# SENSOR.net
KiCad netlist of a schematic drawn in Altium Designer
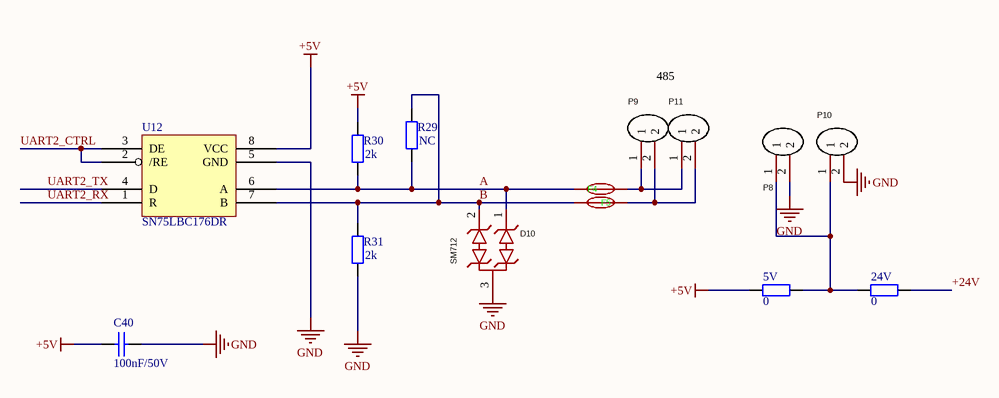
[diagram p0: SENSOR.SchDoc]

(export (version "E")
  (design (tool "Eeschema 10.0.6"))
  (components
    (comp (ref "5V")
      (value "0")
      (footprint "R-0805")
      (description "电阻")
      (fields (field (name "PUBLISHER") "Altium Limited"))
      (libsource (lib "") (part "RES_1"))
    )
    (comp (ref "24V")
      (value "0")
      (footprint "R-0805")
      (description "电阻")
      (fields (field (name "PUBLISHER") "Altium Limited"))
      (libsource (lib "") (part "RES_1"))
    )
    (comp (ref "C40")
      (value "100nF/50V")
      (footprint "C-0805")
      (description "电容")
      (libsource (lib "泰开常用器件") (part "C普通电容"))
    )
    (comp (ref "D10")
      (value "SM712")
      (footprint "SOT-23-3")
      (fields (field (name "MANUFACTURER") "宏迦橙"))
      (libsource (lib "altium-import") (part "root_2_SM712_C7420375_"))
    )
    (comp (ref "F4")
      (value "SMD1206-020-48")
      (footprint "F1206")
      (fields (field (name "MANUFACTURER") "宏嘉诚"))
      (libsource (lib "altium-import") (part "root_0_SMD1206-020-48_"))
    )
    (comp (ref "F5")
      (value "SMD1206-020-48")
      (footprint "F1206")
      (fields (field (name "MANUFACTURER") "宏嘉诚"))
      (libsource (lib "altium-import") (part "root_0_SMD1206-020-48_"))
    )
    (comp (ref "P8")
      (value "WJ500V-5.08-2P")
      (footprint "KF128-2P DG128")
      (fields (field (name "MANUFACTURER") "KANGNEX(康奈克斯电气)"))
      (libsource (lib "泰开常用器件") (part "WJ500V-5.08-2P"))
    )
    (comp (ref "P9")
      (value "WJ500V-5.08-2P")
      (footprint "KF128-2P DG128")
      (fields (field (name "MANUFACTURER") "KANGNEX(康奈克斯电气)"))
      (libsource (lib "泰开常用器件") (part "WJ500V-5.08-2P"))
    )
    (comp (ref "P10")
      (value "WJ500V-5.08-2P")
      (footprint "KF128-2P DG128")
      (fields (field (name "MANUFACTURER") "KANGNEX(康奈克斯电气)"))
      (libsource (lib "泰开常用器件") (part "WJ500V-5.08-2P"))
    )
    (comp (ref "P11")
      (value "WJ500V-5.08-2P")
      (footprint "KF128-2P DG128")
      (fields (field (name "MANUFACTURER") "KANGNEX(康奈克斯电气)"))
      (libsource (lib "泰开常用器件") (part "WJ500V-5.08-2P"))
    )
    (comp (ref "R29")
      (value "NC")
      (footprint "R-0805")
      (description "电阻")
      (fields (field (name "PUBLISHER") "Altium Limited"))
      (libsource (lib "泰开常用器件") (part "RES"))
    )
    (comp (ref "R30")
      (value "2k")
      (footprint "R-0805")
      (description "电阻")
      (fields (field (name "PUBLISHER") "Altium Limited"))
      (libsource (lib "泰开常用器件") (part "RES"))
    )
    (comp (ref "R31")
      (value "2k")
      (footprint "R-0805")
      (description "电阻")
      (fields (field (name "PUBLISHER") "Altium Limited"))
      (libsource (lib "泰开常用器件") (part "RES"))
    )
    (comp (ref "U12")
      (value "SN75LBC176DR")
      (footprint "SOP-8")
      (description "芯片")
      (libsource (lib "芯片") (part "75LBC176"))
    )
  )
  (nets
    (net (code "1") (name "+5V") (class "Default")
      (node (ref "5V") (pin "2") (pinfunction "2_2") (pintype "passive"))
      (node (ref "C40") (pin "1") (pinfunction "1_1") (pintype "passive"))
      (node (ref "R30") (pin "2") (pinfunction "2_2") (pintype "passive"))
      (node (ref "U12") (pin "8") (pinfunction "VCC_8") (pintype "passive"))
    )
    (net (code "2") (name "/+24V") (class "Default")
      (node (ref "24V") (pin "1") (pinfunction "1_1") (pintype "passive"))
    )
    (net (code "3") (name "/A") (class "Default")
      (node (ref "D10") (pin "1") (pinfunction "1_1") (pintype "passive"))
      (node (ref "F4") (pin "1") (pinfunction "1_1") (pintype "passive"))
      (node (ref "R29") (pin "1") (pinfunction "1_1") (pintype "passive"))
      (node (ref "R30") (pin "1") (pinfunction "1_1") (pintype "passive"))
      (node (ref "U12") (pin "6") (pinfunction "A_6") (pintype "passive"))
    )
    (net (code "4") (name "/B") (class "Default")
      (node (ref "D10") (pin "2") (pinfunction "2_2") (pintype "passive"))
      (node (ref "F5") (pin "1") (pinfunction "1_1") (pintype "passive"))
      (node (ref "R29") (pin "2") (pinfunction "2_2") (pintype "passive"))
      (node (ref "R31") (pin "2") (pinfunction "2_2") (pintype "passive"))
      (node (ref "U12") (pin "7") (pinfunction "B_7") (pintype "passive"))
    )
    (net (code "5") (name "/UART2_CTRL") (class "Default")
      (node (ref "U12") (pin "2") (pinfunction "/RE_2") (pintype "passive"))
      (node (ref "U12") (pin "3") (pinfunction "DE_3") (pintype "passive"))
    )
    (net (code "6") (name "/UART2_RX") (class "Default")
      (node (ref "U12") (pin "1") (pinfunction "R_1") (pintype "passive"))
    )
    (net (code "7") (name "/UART2_TX") (class "Default")
      (node (ref "U12") (pin "4") (pinfunction "D_4") (pintype "passive"))
    )
    (net (code "8") (name "GND") (class "Default")
      (node (ref "C40") (pin "2") (pinfunction "2_2") (pintype "passive"))
      (node (ref "D10") (pin "3") (pinfunction "3_3") (pintype "passive"))
      (node (ref "P10") (pin "2") (pinfunction "2_2") (pintype "passive"))
      (node (ref "P8") (pin "2") (pinfunction "2_2") (pintype "passive"))
      (node (ref "R31") (pin "1") (pinfunction "1_1") (pintype "passive"))
      (node (ref "U12") (pin "5") (pinfunction "GND_5") (pintype "passive"))
    )
    (net (code "9") (name "Net-(24V-Pad2)") (class "Default")
      (node (ref "24V") (pin "2") (pinfunction "2_2") (pintype "passive"))
      (node (ref "5V") (pin "1") (pinfunction "1_1") (pintype "passive"))
      (node (ref "P10") (pin "1") (pinfunction "1_1") (pintype "passive"))
      (node (ref "P8") (pin "1") (pinfunction "1_1") (pintype "passive"))
    )
    (net (code "10") (name "Net-(F4-Pad2)") (class "Default")
      (node (ref "F4") (pin "2") (pinfunction "2_2") (pintype "passive"))
      (node (ref "P11") (pin "1") (pinfunction "1_1") (pintype "passive"))
      (node (ref "P9") (pin "1") (pinfunction "1_1") (pintype "passive"))
    )
    (net (code "11") (name "Net-(F5-Pad2)") (class "Default")
      (node (ref "F5") (pin "2") (pinfunction "2_2") (pintype "passive"))
      (node (ref "P11") (pin "2") (pinfunction "2_2") (pintype "passive"))
      (node (ref "P9") (pin "2") (pinfunction "2_2") (pintype "passive"))
    )
  )
)
